# AnalogIntensityBar.net
KiCad netlist of a schematic drawn in EAGLE
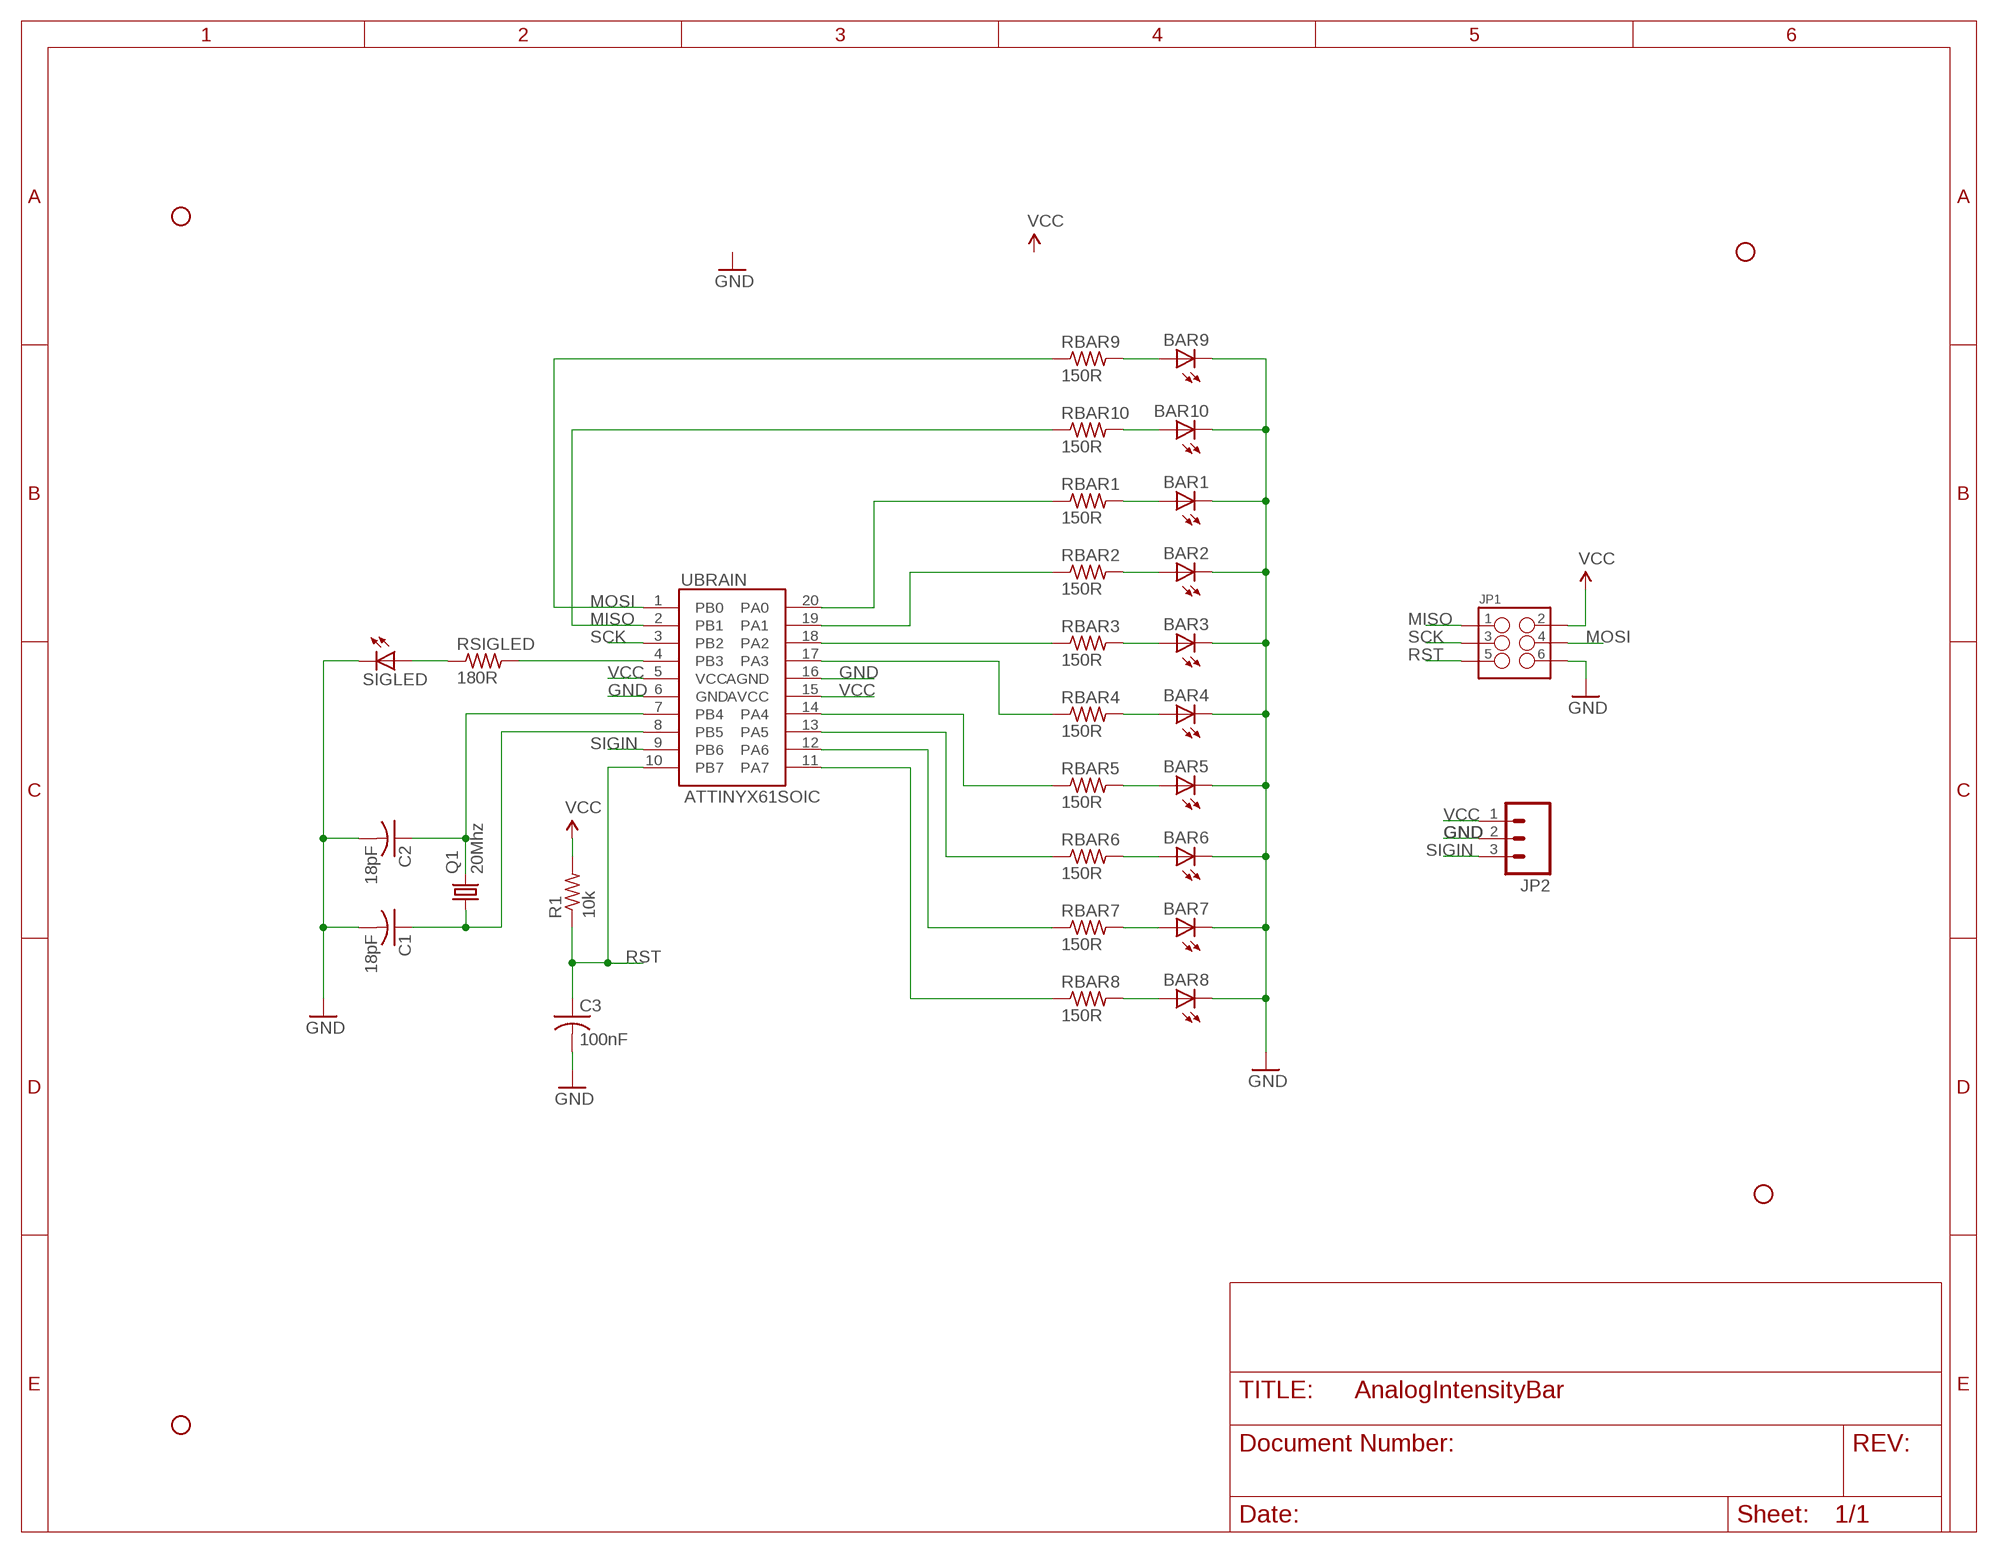
[diagram p0: schematic, sheet 1]

(export (version "E")
  (design (tool "Eeschema 10.0.6"))
  (components
    (comp (ref "BAR1")
      (value "LEDCHIP-LED0603")
      (footprint "eagle-import:CHIP-LED0603")
      (libsource (lib "eagle-import") (part "LEDCHIP-LED0603"))
    )
    (comp (ref "BAR2")
      (value "LEDCHIP-LED0603")
      (footprint "eagle-import:CHIP-LED0603")
      (libsource (lib "eagle-import") (part "LEDCHIP-LED0603"))
    )
    (comp (ref "BAR3")
      (value "LEDCHIP-LED0603")
      (footprint "eagle-import:CHIP-LED0603")
      (libsource (lib "eagle-import") (part "LEDCHIP-LED0603"))
    )
    (comp (ref "BAR4")
      (value "LEDCHIP-LED0603")
      (footprint "eagle-import:CHIP-LED0603")
      (libsource (lib "eagle-import") (part "LEDCHIP-LED0603"))
    )
    (comp (ref "BAR5")
      (value "LEDCHIP-LED0603")
      (footprint "eagle-import:CHIP-LED0603")
      (libsource (lib "eagle-import") (part "LEDCHIP-LED0603"))
    )
    (comp (ref "BAR6")
      (value "LEDCHIP-LED0603")
      (footprint "eagle-import:CHIP-LED0603")
      (libsource (lib "eagle-import") (part "LEDCHIP-LED0603"))
    )
    (comp (ref "BAR7")
      (value "LEDCHIP-LED0603")
      (footprint "eagle-import:CHIP-LED0603")
      (libsource (lib "eagle-import") (part "LEDCHIP-LED0603"))
    )
    (comp (ref "BAR8")
      (value "LEDCHIP-LED0603")
      (footprint "eagle-import:CHIP-LED0603")
      (libsource (lib "eagle-import") (part "LEDCHIP-LED0603"))
    )
    (comp (ref "BAR9")
      (value "LEDCHIP-LED0603")
      (footprint "eagle-import:CHIP-LED0603")
      (libsource (lib "eagle-import") (part "LEDCHIP-LED0603"))
    )
    (comp (ref "BAR10")
      (value "LEDCHIP-LED0603")
      (footprint "eagle-import:CHIP-LED0603")
      (libsource (lib "eagle-import") (part "LEDCHIP-LED0603"))
    )
    (comp (ref "C1")
      (value "18pF")
      (footprint "eagle-import:C0402")
      (libsource (lib "eagle-import") (part "C-USC0402"))
    )
    (comp (ref "C2")
      (value "18pF")
      (footprint "eagle-import:C0402")
      (libsource (lib "eagle-import") (part "C-USC0402"))
    )
    (comp (ref "C3")
      (value "100nF")
      (footprint "eagle-import:C0402")
      (libsource (lib "eagle-import") (part "C-USC0402"))
    )
    (comp (ref "JP1")
      (value "M03X22X3_SILK_SM")
      (footprint "eagle-import:2X3")
      (libsource (lib "eagle-import") (part "M03X22X3_SILK_SM"))
    )
    (comp (ref "JP2")
      (value "M03PTH")
      (footprint "eagle-import:1X03")
      (libsource (lib "eagle-import") (part "M03PTH"))
    )
    (comp (ref "Q1")
      (value "20Mhz")
      (footprint "eagle-import:HC49UP")
      (libsource (lib "eagle-import") (part "CRYSTALHC49UP"))
    )
    (comp (ref "R1")
      (value "10k")
      (footprint "eagle-import:R0402")
      (libsource (lib "eagle-import") (part "R-US_R0402"))
    )
    (comp (ref "RBAR1")
      (value "150R")
      (footprint "eagle-import:R0603")
      (libsource (lib "eagle-import") (part "R-US_R0603"))
    )
    (comp (ref "RBAR2")
      (value "150R")
      (footprint "eagle-import:R0603")
      (libsource (lib "eagle-import") (part "R-US_R0603"))
    )
    (comp (ref "RBAR3")
      (value "150R")
      (footprint "eagle-import:R0603")
      (libsource (lib "eagle-import") (part "R-US_R0603"))
    )
    (comp (ref "RBAR4")
      (value "150R")
      (footprint "eagle-import:R0603")
      (libsource (lib "eagle-import") (part "R-US_R0603"))
    )
    (comp (ref "RBAR5")
      (value "150R")
      (footprint "eagle-import:R0603")
      (libsource (lib "eagle-import") (part "R-US_R0603"))
    )
    (comp (ref "RBAR6")
      (value "150R")
      (footprint "eagle-import:R0603")
      (libsource (lib "eagle-import") (part "R-US_R0603"))
    )
    (comp (ref "RBAR7")
      (value "150R")
      (footprint "eagle-import:R0603")
      (libsource (lib "eagle-import") (part "R-US_R0603"))
    )
    (comp (ref "RBAR8")
      (value "150R")
      (footprint "eagle-import:R0603")
      (libsource (lib "eagle-import") (part "R-US_R0603"))
    )
    (comp (ref "RBAR9")
      (value "150R")
      (footprint "eagle-import:R0603")
      (libsource (lib "eagle-import") (part "R-US_R0603"))
    )
    (comp (ref "RBAR10")
      (value "150R")
      (footprint "eagle-import:R0603")
      (libsource (lib "eagle-import") (part "R-US_R0603"))
    )
    (comp (ref "RSIGLED")
      (value "180R")
      (footprint "eagle-import:R0603")
      (libsource (lib "eagle-import") (part "R-US_R0603"))
    )
    (comp (ref "SIGLED")
      (value "LEDCHIP-LED0805")
      (footprint "eagle-import:CHIP-LED0805")
      (libsource (lib "eagle-import") (part "LEDCHIP-LED0805"))
    )
    (comp (ref "STANDOFF1")
      (value "STAND-OFF")
      (footprint "eagle-import:STAND-OFF")
      (libsource (lib "eagle-import") (part "STAND-OFF"))
    )
    (comp (ref "STANDOFF2")
      (value "STAND-OFF")
      (footprint "eagle-import:STAND-OFF")
      (libsource (lib "eagle-import") (part "STAND-OFF"))
    )
    (comp (ref "STANDOFF3")
      (value "STAND-OFF")
      (footprint "eagle-import:STAND-OFF")
      (libsource (lib "eagle-import") (part "STAND-OFF"))
    )
    (comp (ref "STANDOFF4")
      (value "STAND-OFF")
      (footprint "eagle-import:STAND-OFF")
      (libsource (lib "eagle-import") (part "STAND-OFF"))
    )
    (comp (ref "UBRAIN")
      (value "ATTINYX61SOIC")
      (footprint "eagle-import:20S2")
      (libsource (lib "eagle-import") (part "ATTINYX61SOIC"))
    )
  )
  (nets
    (net (code "1") (name "/MISO") (class "Default")
      (node (ref "JP1") (pin "1") (pinfunction "1_1") (pintype "bidirectional"))
      (node (ref "RBAR10") (pin "1") (pinfunction "1_1") (pintype "passive"))
      (node (ref "UBRAIN") (pin "2") (pinfunction "PB1_2") (pintype "bidirectional"))
    )
    (net (code "2") (name "/MOSI") (class "Default")
      (node (ref "JP1") (pin "4") (pinfunction "4_4") (pintype "bidirectional"))
      (node (ref "RBAR9") (pin "1") (pinfunction "1_1") (pintype "passive"))
      (node (ref "UBRAIN") (pin "1") (pinfunction "PB0_1") (pintype "bidirectional"))
    )
    (net (code "3") (name "/RST") (class "Default")
      (node (ref "C3") (pin "1") (pinfunction "1_1") (pintype "passive"))
      (node (ref "JP1") (pin "5") (pinfunction "5_5") (pintype "bidirectional"))
      (node (ref "R1") (pin "1") (pinfunction "1_1") (pintype "passive"))
      (node (ref "UBRAIN") (pin "10") (pinfunction "PB7_10") (pintype "bidirectional"))
    )
    (net (code "4") (name "/SCK") (class "Default")
      (node (ref "JP1") (pin "3") (pinfunction "3_3") (pintype "bidirectional"))
      (node (ref "UBRAIN") (pin "3") (pinfunction "PB2_3") (pintype "bidirectional"))
    )
    (net (code "5") (name "/SIGIN") (class "Default")
      (node (ref "JP2") (pin "3") (pinfunction "3_3") (pintype "passive"))
      (node (ref "UBRAIN") (pin "9") (pinfunction "PB6_9") (pintype "bidirectional"))
    )
    (net (code "6") (name "GND") (class "Default")
      (node (ref "BAR1") (pin "C") (pinfunction "C_C") (pintype "passive"))
      (node (ref "BAR10") (pin "C") (pinfunction "C_C") (pintype "passive"))
      (node (ref "BAR2") (pin "C") (pinfunction "C_C") (pintype "passive"))
      (node (ref "BAR3") (pin "C") (pinfunction "C_C") (pintype "passive"))
      (node (ref "BAR4") (pin "C") (pinfunction "C_C") (pintype "passive"))
      (node (ref "BAR5") (pin "C") (pinfunction "C_C") (pintype "passive"))
      (node (ref "BAR6") (pin "C") (pinfunction "C_C") (pintype "passive"))
      (node (ref "BAR7") (pin "C") (pinfunction "C_C") (pintype "passive"))
      (node (ref "BAR8") (pin "C") (pinfunction "C_C") (pintype "passive"))
      (node (ref "BAR9") (pin "C") (pinfunction "C_C") (pintype "passive"))
      (node (ref "C1") (pin "2") (pinfunction "2_2") (pintype "passive"))
      (node (ref "C2") (pin "2") (pinfunction "2_2") (pintype "passive"))
      (node (ref "C3") (pin "2") (pinfunction "2_2") (pintype "passive"))
      (node (ref "JP1") (pin "6") (pinfunction "6_6") (pintype "bidirectional"))
      (node (ref "JP2") (pin "2") (pinfunction "2_2") (pintype "passive"))
      (node (ref "SIGLED") (pin "C") (pinfunction "C_C") (pintype "passive"))
      (node (ref "UBRAIN") (pin "16") (pinfunction "AGND_16") (pintype "bidirectional"))
      (node (ref "UBRAIN") (pin "6") (pinfunction "GND_6") (pintype "bidirectional"))
    )
    (net (code "7") (name "Net-(BAR1-PadA)") (class "Default")
      (node (ref "BAR1") (pin "A") (pinfunction "A_A") (pintype "passive"))
      (node (ref "RBAR1") (pin "2") (pinfunction "2_2") (pintype "passive"))
    )
    (net (code "8") (name "Net-(BAR2-PadA)") (class "Default")
      (node (ref "BAR2") (pin "A") (pinfunction "A_A") (pintype "passive"))
      (node (ref "RBAR2") (pin "2") (pinfunction "2_2") (pintype "passive"))
    )
    (net (code "9") (name "Net-(BAR3-PadA)") (class "Default")
      (node (ref "BAR3") (pin "A") (pinfunction "A_A") (pintype "passive"))
      (node (ref "RBAR3") (pin "2") (pinfunction "2_2") (pintype "passive"))
    )
    (net (code "10") (name "Net-(BAR4-PadA)") (class "Default")
      (node (ref "BAR4") (pin "A") (pinfunction "A_A") (pintype "passive"))
      (node (ref "RBAR4") (pin "2") (pinfunction "2_2") (pintype "passive"))
    )
    (net (code "11") (name "Net-(BAR5-PadA)") (class "Default")
      (node (ref "BAR5") (pin "A") (pinfunction "A_A") (pintype "passive"))
      (node (ref "RBAR5") (pin "2") (pinfunction "2_2") (pintype "passive"))
    )
    (net (code "12") (name "Net-(BAR6-PadA)") (class "Default")
      (node (ref "BAR6") (pin "A") (pinfunction "A_A") (pintype "passive"))
      (node (ref "RBAR6") (pin "2") (pinfunction "2_2") (pintype "passive"))
    )
    (net (code "13") (name "Net-(BAR7-PadA)") (class "Default")
      (node (ref "BAR7") (pin "A") (pinfunction "A_A") (pintype "passive"))
      (node (ref "RBAR7") (pin "2") (pinfunction "2_2") (pintype "passive"))
    )
    (net (code "14") (name "Net-(BAR8-PadA)") (class "Default")
      (node (ref "BAR8") (pin "A") (pinfunction "A_A") (pintype "passive"))
      (node (ref "RBAR8") (pin "2") (pinfunction "2_2") (pintype "passive"))
    )
    (net (code "15") (name "Net-(BAR9-PadA)") (class "Default")
      (node (ref "BAR9") (pin "A") (pinfunction "A_A") (pintype "passive"))
      (node (ref "RBAR9") (pin "2") (pinfunction "2_2") (pintype "passive"))
    )
    (net (code "16") (name "Net-(BAR10-PadA)") (class "Default")
      (node (ref "BAR10") (pin "A") (pinfunction "A_A") (pintype "passive"))
      (node (ref "RBAR10") (pin "2") (pinfunction "2_2") (pintype "passive"))
    )
    (net (code "17") (name "Net-(RSIGLED-Pad1)") (class "Default")
      (node (ref "RSIGLED") (pin "1") (pinfunction "1_1") (pintype "passive"))
      (node (ref "SIGLED") (pin "A") (pinfunction "A_A") (pintype "passive"))
    )
    (net (code "18") (name "Net-(UBRAIN-PA0)") (class "Default")
      (node (ref "RBAR1") (pin "1") (pinfunction "1_1") (pintype "passive"))
      (node (ref "UBRAIN") (pin "20") (pinfunction "PA0_20") (pintype "bidirectional"))
    )
    (net (code "19") (name "Net-(UBRAIN-PA1)") (class "Default")
      (node (ref "RBAR2") (pin "1") (pinfunction "1_1") (pintype "passive"))
      (node (ref "UBRAIN") (pin "19") (pinfunction "PA1_19") (pintype "bidirectional"))
    )
    (net (code "20") (name "Net-(UBRAIN-PA2)") (class "Default")
      (node (ref "RBAR3") (pin "1") (pinfunction "1_1") (pintype "passive"))
      (node (ref "UBRAIN") (pin "18") (pinfunction "PA2_18") (pintype "bidirectional"))
    )
    (net (code "21") (name "Net-(UBRAIN-PA3)") (class "Default")
      (node (ref "RBAR4") (pin "1") (pinfunction "1_1") (pintype "passive"))
      (node (ref "UBRAIN") (pin "17") (pinfunction "PA3_17") (pintype "bidirectional"))
    )
    (net (code "22") (name "Net-(UBRAIN-PA4)") (class "Default")
      (node (ref "RBAR5") (pin "1") (pinfunction "1_1") (pintype "passive"))
      (node (ref "UBRAIN") (pin "14") (pinfunction "PA4_14") (pintype "bidirectional"))
    )
    (net (code "23") (name "Net-(UBRAIN-PA5)") (class "Default")
      (node (ref "RBAR6") (pin "1") (pinfunction "1_1") (pintype "passive"))
      (node (ref "UBRAIN") (pin "13") (pinfunction "PA5_13") (pintype "bidirectional"))
    )
    (net (code "24") (name "Net-(UBRAIN-PA6)") (class "Default")
      (node (ref "RBAR7") (pin "1") (pinfunction "1_1") (pintype "passive"))
      (node (ref "UBRAIN") (pin "12") (pinfunction "PA6_12") (pintype "bidirectional"))
    )
    (net (code "25") (name "Net-(UBRAIN-PA7)") (class "Default")
      (node (ref "RBAR8") (pin "1") (pinfunction "1_1") (pintype "passive"))
      (node (ref "UBRAIN") (pin "11") (pinfunction "PA7_11") (pintype "bidirectional"))
    )
    (net (code "26") (name "Net-(UBRAIN-PB3)") (class "Default")
      (node (ref "RSIGLED") (pin "2") (pinfunction "2_2") (pintype "passive"))
      (node (ref "UBRAIN") (pin "4") (pinfunction "PB3_4") (pintype "bidirectional"))
    )
    (net (code "27") (name "Net-(UBRAIN-PB4)") (class "Default")
      (node (ref "C2") (pin "1") (pinfunction "1_1") (pintype "passive"))
      (node (ref "Q1") (pin "2") (pinfunction "2_2") (pintype "passive"))
      (node (ref "UBRAIN") (pin "7") (pinfunction "PB4_7") (pintype "bidirectional"))
    )
    (net (code "28") (name "Net-(UBRAIN-PB5)") (class "Default")
      (node (ref "C1") (pin "1") (pinfunction "1_1") (pintype "passive"))
      (node (ref "Q1") (pin "1") (pinfunction "1_1") (pintype "passive"))
      (node (ref "UBRAIN") (pin "8") (pinfunction "PB5_8") (pintype "bidirectional"))
    )
    (net (code "29") (name "VCC") (class "Default")
      (node (ref "JP1") (pin "2") (pinfunction "2_2") (pintype "bidirectional"))
      (node (ref "JP2") (pin "1") (pinfunction "1_1") (pintype "passive"))
      (node (ref "R1") (pin "2") (pinfunction "2_2") (pintype "passive"))
      (node (ref "UBRAIN") (pin "15") (pinfunction "AVCC_15") (pintype "bidirectional"))
      (node (ref "UBRAIN") (pin "5") (pinfunction "VCC_5") (pintype "bidirectional"))
    )
  )
)
